# FitNibble_v2.net
KiCad netlist of a schematic drawn in EAGLE
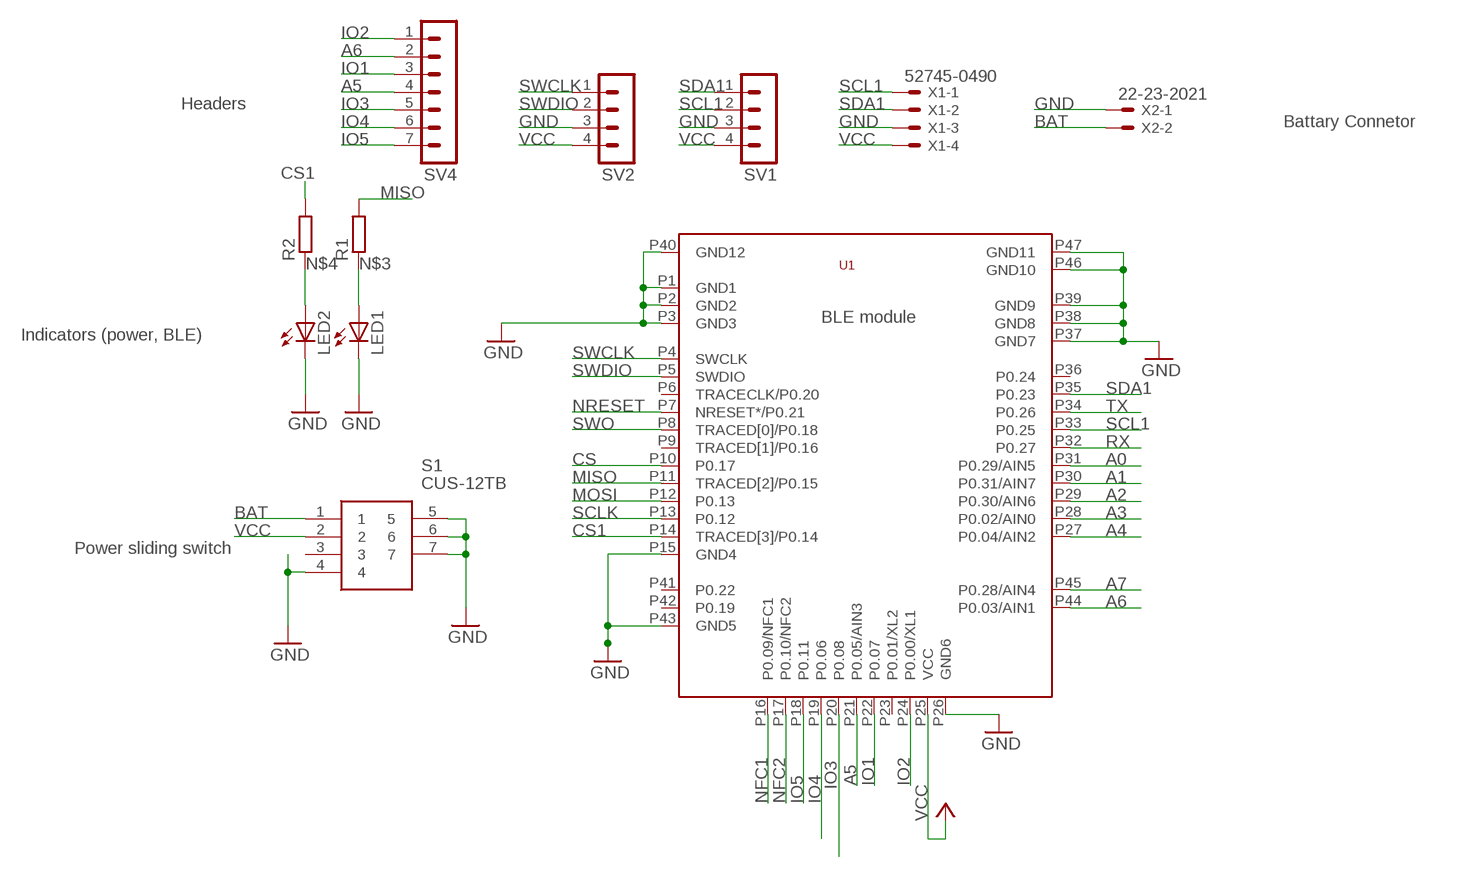
[diagram p0: schematic, sheet 1]

(export (version "E")
  (design (tool "Eeschema 10.0.6"))
  (components
    (comp (ref "LED1")
      (value "LED_ESML0603")
      (footprint "eagle-import:LED_SML0603")
      (libsource (lib "eagle-import") (part "LED_ESML0603"))
    )
    (comp (ref "LED2")
      (value "LED_ESML0603")
      (footprint "eagle-import:LED_SML0603")
      (libsource (lib "eagle-import") (part "LED_ESML0603"))
    )
    (comp (ref "R1")
      (value "R-EU_R0603")
      (footprint "eagle-import:R0603")
      (libsource (lib "eagle-import") (part "R-EU_R0603"))
    )
    (comp (ref "R2")
      (value "R-EU_R0603")
      (footprint "eagle-import:R0603")
      (libsource (lib "eagle-import") (part "R-EU_R0603"))
    )
    (comp (ref "S1")
      (value "CUS-12TB")
      (footprint "eagle-import:CUS-12B")
      (libsource (lib "eagle-import") (part "CUS-12TB"))
    )
    (comp (ref "SV1")
      (value "MA04-1")
      (footprint "eagle-import:MA04-1")
      (libsource (lib "eagle-import") (part "MA04-1"))
    )
    (comp (ref "SV2")
      (value "MA04-1")
      (footprint "eagle-import:MA04-1")
      (libsource (lib "eagle-import") (part "MA04-1"))
    )
    (comp (ref "SV4")
      (value "MA07-1")
      (footprint "eagle-import:MA07-1")
      (libsource (lib "eagle-import") (part "MA07-1"))
    )
    (comp (ref "U1")
      (value "BMD-350")
      (footprint "eagle-import:BMD-350")
      (libsource (lib "eagle-import") (part "BMD-350"))
    )
    (comp (ref "X1")
      (value "52745-0490")
      (footprint "eagle-import:52745-0490")
      (libsource (lib "eagle-import") (part "52745-0490"))
    )
    (comp (ref "X2")
      (value "22-23-2021")
      (footprint "eagle-import:22-23-2021")
      (fields (field (name "MF") "MOLEX"))
      (libsource (lib "eagle-import") (part "22-23-2021"))
    )
  )
  (nets
    (net (code "1") (name "/A0") (class "Default")
      (node (ref "U1") (pin "P31") (pinfunction "P0.29/AIN5_P31") (pintype "bidirectional"))
    )
    (net (code "2") (name "/A1") (class "Default")
      (node (ref "U1") (pin "P30") (pinfunction "P0.31/AIN7_P30") (pintype "bidirectional"))
    )
    (net (code "3") (name "/A2") (class "Default")
      (node (ref "U1") (pin "P29") (pinfunction "P0.30/AIN6_P29") (pintype "bidirectional"))
    )
    (net (code "4") (name "/A3") (class "Default")
      (node (ref "U1") (pin "P28") (pinfunction "P0.02/AIN0_P28") (pintype "bidirectional"))
    )
    (net (code "5") (name "/A4") (class "Default")
      (node (ref "U1") (pin "P27") (pinfunction "P0.04/AIN2_P27") (pintype "bidirectional"))
    )
    (net (code "6") (name "/A5") (class "Default")
      (node (ref "SV4") (pin "4") (pinfunction "4_4") (pintype "passive"))
      (node (ref "U1") (pin "P21") (pinfunction "P0.05/AIN3_P21") (pintype "bidirectional"))
    )
    (net (code "7") (name "/A6") (class "Default")
      (node (ref "SV4") (pin "2") (pinfunction "2_2") (pintype "passive"))
      (node (ref "U1") (pin "P44") (pinfunction "P0.03/AIN1_P44") (pintype "bidirectional"))
    )
    (net (code "8") (name "/A7") (class "Default")
      (node (ref "U1") (pin "P45") (pinfunction "P0.28/AIN4_P45") (pintype "bidirectional"))
    )
    (net (code "9") (name "/BAT") (class "Default")
      (node (ref "S1") (pin "1") (pinfunction "1_1") (pintype "bidirectional"))
      (node (ref "X2") (pin "2") (pinfunction "S_2") (pintype "passive"))
    )
    (net (code "10") (name "/CS") (class "Default")
      (node (ref "U1") (pin "P10") (pinfunction "P0.17_P10") (pintype "bidirectional"))
    )
    (net (code "11") (name "/CS1") (class "Default")
      (node (ref "R2") (pin "2") (pinfunction "2_2") (pintype "passive"))
      (node (ref "U1") (pin "P14") (pinfunction "TRACED[3]/P0.14_P14") (pintype "bidirectional"))
    )
    (net (code "12") (name "/IO1") (class "Default")
      (node (ref "SV4") (pin "3") (pinfunction "3_3") (pintype "passive"))
      (node (ref "U1") (pin "P22") (pinfunction "P0.07_P22") (pintype "bidirectional"))
    )
    (net (code "13") (name "/IO2") (class "Default")
      (node (ref "SV4") (pin "1") (pinfunction "1_1") (pintype "passive"))
      (node (ref "U1") (pin "P24") (pinfunction "P0.00/XL1_P24") (pintype "bidirectional"))
    )
    (net (code "14") (name "/IO3") (class "Default")
      (node (ref "SV4") (pin "5") (pinfunction "5_5") (pintype "passive"))
      (node (ref "U1") (pin "P20") (pinfunction "P0.08_P20") (pintype "bidirectional"))
    )
    (net (code "15") (name "/IO4") (class "Default")
      (node (ref "SV4") (pin "6") (pinfunction "6_6") (pintype "passive"))
      (node (ref "U1") (pin "P19") (pinfunction "P0.06_P19") (pintype "bidirectional"))
    )
    (net (code "16") (name "/IO5") (class "Default")
      (node (ref "SV4") (pin "7") (pinfunction "7_7") (pintype "passive"))
      (node (ref "U1") (pin "P18") (pinfunction "P0.11_P18") (pintype "bidirectional"))
    )
    (net (code "17") (name "/MISO") (class "Default")
      (node (ref "R1") (pin "2") (pinfunction "2_2") (pintype "passive"))
      (node (ref "U1") (pin "P11") (pinfunction "TRACED[2]/P0.15_P11") (pintype "bidirectional"))
    )
    (net (code "18") (name "/MOSI") (class "Default")
      (node (ref "U1") (pin "P12") (pinfunction "P0.13_P12") (pintype "bidirectional"))
    )
    (net (code "19") (name "/N$3") (class "Default")
      (node (ref "LED1") (pin "A") (pinfunction "A_A") (pintype "passive"))
      (node (ref "R1") (pin "1") (pinfunction "1_1") (pintype "passive"))
    )
    (net (code "20") (name "/N$4") (class "Default")
      (node (ref "LED2") (pin "A") (pinfunction "A_A") (pintype "passive"))
      (node (ref "R2") (pin "1") (pinfunction "1_1") (pintype "passive"))
    )
    (net (code "21") (name "/NFC1") (class "Default")
      (node (ref "U1") (pin "P16") (pinfunction "P0.09/NFC1_P16") (pintype "bidirectional"))
    )
    (net (code "22") (name "/NFC2") (class "Default")
      (node (ref "U1") (pin "P17") (pinfunction "P0.10/NFC2_P17") (pintype "bidirectional"))
    )
    (net (code "23") (name "/NRESET") (class "Default")
      (node (ref "U1") (pin "P7") (pinfunction "NRESET*/P0.21_P7") (pintype "bidirectional"))
    )
    (net (code "24") (name "/RX") (class "Default")
      (node (ref "U1") (pin "P32") (pinfunction "P0.27_P32") (pintype "bidirectional"))
    )
    (net (code "25") (name "/SCL1") (class "Default")
      (node (ref "SV1") (pin "2") (pinfunction "2_2") (pintype "passive"))
      (node (ref "U1") (pin "P33") (pinfunction "P0.25_P33") (pintype "bidirectional"))
      (node (ref "X1") (pin "1") (pinfunction "S_1") (pintype "passive"))
    )
    (net (code "26") (name "/SCLK") (class "Default")
      (node (ref "U1") (pin "P13") (pinfunction "P0.12_P13") (pintype "bidirectional"))
    )
    (net (code "27") (name "/SDA1") (class "Default")
      (node (ref "SV1") (pin "1") (pinfunction "1_1") (pintype "passive"))
      (node (ref "U1") (pin "P35") (pinfunction "P0.23_P35") (pintype "bidirectional"))
      (node (ref "X1") (pin "2") (pinfunction "S_2") (pintype "passive"))
    )
    (net (code "28") (name "/SWCLK") (class "Default")
      (node (ref "SV2") (pin "1") (pinfunction "1_1") (pintype "passive"))
      (node (ref "U1") (pin "P4") (pinfunction "SWCLK_P4") (pintype "bidirectional"))
    )
    (net (code "29") (name "/SWDIO") (class "Default")
      (node (ref "SV2") (pin "2") (pinfunction "2_2") (pintype "passive"))
      (node (ref "U1") (pin "P5") (pinfunction "SWDIO_P5") (pintype "bidirectional"))
    )
    (net (code "30") (name "/SWO") (class "Default")
      (node (ref "U1") (pin "P8") (pinfunction "TRACED[0]/P0.18_P8") (pintype "bidirectional"))
    )
    (net (code "31") (name "/TX") (class "Default")
      (node (ref "U1") (pin "P34") (pinfunction "P0.26_P34") (pintype "bidirectional"))
    )
    (net (code "32") (name "GND") (class "Default")
      (node (ref "LED1") (pin "C") (pinfunction "C_C") (pintype "passive"))
      (node (ref "LED2") (pin "C") (pinfunction "C_C") (pintype "passive"))
      (node (ref "S1") (pin "4") (pinfunction "4_4") (pintype "bidirectional"))
      (node (ref "S1") (pin "5") (pinfunction "5_5") (pintype "bidirectional"))
      (node (ref "S1") (pin "6") (pinfunction "6_6") (pintype "bidirectional"))
      (node (ref "S1") (pin "7") (pinfunction "7_7") (pintype "bidirectional"))
      (node (ref "SV1") (pin "3") (pinfunction "3_3") (pintype "passive"))
      (node (ref "SV2") (pin "3") (pinfunction "3_3") (pintype "passive"))
      (node (ref "U1") (pin "P1") (pinfunction "GND1_P1") (pintype "bidirectional"))
      (node (ref "U1") (pin "P15") (pinfunction "GND4_P15") (pintype "bidirectional"))
      (node (ref "U1") (pin "P2") (pinfunction "GND2_P2") (pintype "bidirectional"))
      (node (ref "U1") (pin "P26") (pinfunction "GND6_P26") (pintype "bidirectional"))
      (node (ref "U1") (pin "P3") (pinfunction "GND3_P3") (pintype "bidirectional"))
      (node (ref "U1") (pin "P37") (pinfunction "GND7_P37") (pintype "bidirectional"))
      (node (ref "U1") (pin "P38") (pinfunction "GND8_P38") (pintype "bidirectional"))
      (node (ref "U1") (pin "P39") (pinfunction "GND9_P39") (pintype "bidirectional"))
      (node (ref "U1") (pin "P40") (pinfunction "GND12_P40") (pintype "bidirectional"))
      (node (ref "U1") (pin "P43") (pinfunction "GND5_P43") (pintype "bidirectional"))
      (node (ref "U1") (pin "P46") (pinfunction "GND10_P46") (pintype "bidirectional"))
      (node (ref "U1") (pin "P47") (pinfunction "GND11_P47") (pintype "bidirectional"))
      (node (ref "X1") (pin "3") (pinfunction "S_3") (pintype "passive"))
      (node (ref "X2") (pin "1") (pinfunction "S_1") (pintype "passive"))
    )
    (net (code "33") (name "VCC") (class "Default")
      (node (ref "S1") (pin "2") (pinfunction "2_2") (pintype "bidirectional"))
      (node (ref "SV1") (pin "4") (pinfunction "4_4") (pintype "passive"))
      (node (ref "SV2") (pin "4") (pinfunction "4_4") (pintype "passive"))
      (node (ref "U1") (pin "P25") (pinfunction "VCC_P25") (pintype "bidirectional"))
      (node (ref "X1") (pin "4") (pinfunction "S_4") (pintype "passive"))
    )
    (net (code "34") (name "unconnected-(S1-Pad3)") (class "Default")
      (node (ref "S1") (pin "3") (pinfunction "3_3") (pintype "bidirectional"))
    )
    (net (code "35") (name "unconnected-(U1-P0.01{slash}XL2-PadP23)") (class "Default")
      (node (ref "U1") (pin "P23") (pinfunction "P0.01/XL2_P23") (pintype "bidirectional"))
    )
    (net (code "36") (name "unconnected-(U1-P0.19-PadP42)") (class "Default")
      (node (ref "U1") (pin "P42") (pinfunction "P0.19_P42") (pintype "bidirectional"))
    )
    (net (code "37") (name "unconnected-(U1-P0.22-PadP41)") (class "Default")
      (node (ref "U1") (pin "P41") (pinfunction "P0.22_P41") (pintype "bidirectional"))
    )
    (net (code "38") (name "unconnected-(U1-P0.24-PadP36)") (class "Default")
      (node (ref "U1") (pin "P36") (pinfunction "P0.24_P36") (pintype "bidirectional"))
    )
    (net (code "39") (name "unconnected-(U1-TRACECLK{slash}P0.20-PadP6)") (class "Default")
      (node (ref "U1") (pin "P6") (pinfunction "TRACECLK/P0.20_P6") (pintype "bidirectional"))
    )
    (net (code "40") (name "unconnected-(U1-TRACED[1]{slash}P0.16-PadP9)") (class "Default")
      (node (ref "U1") (pin "P9") (pinfunction "TRACED[1]/P0.16_P9") (pintype "bidirectional"))
    )
  )
)
